# analog3.net
KiCad netlist of a schematic drawn in EAGLE
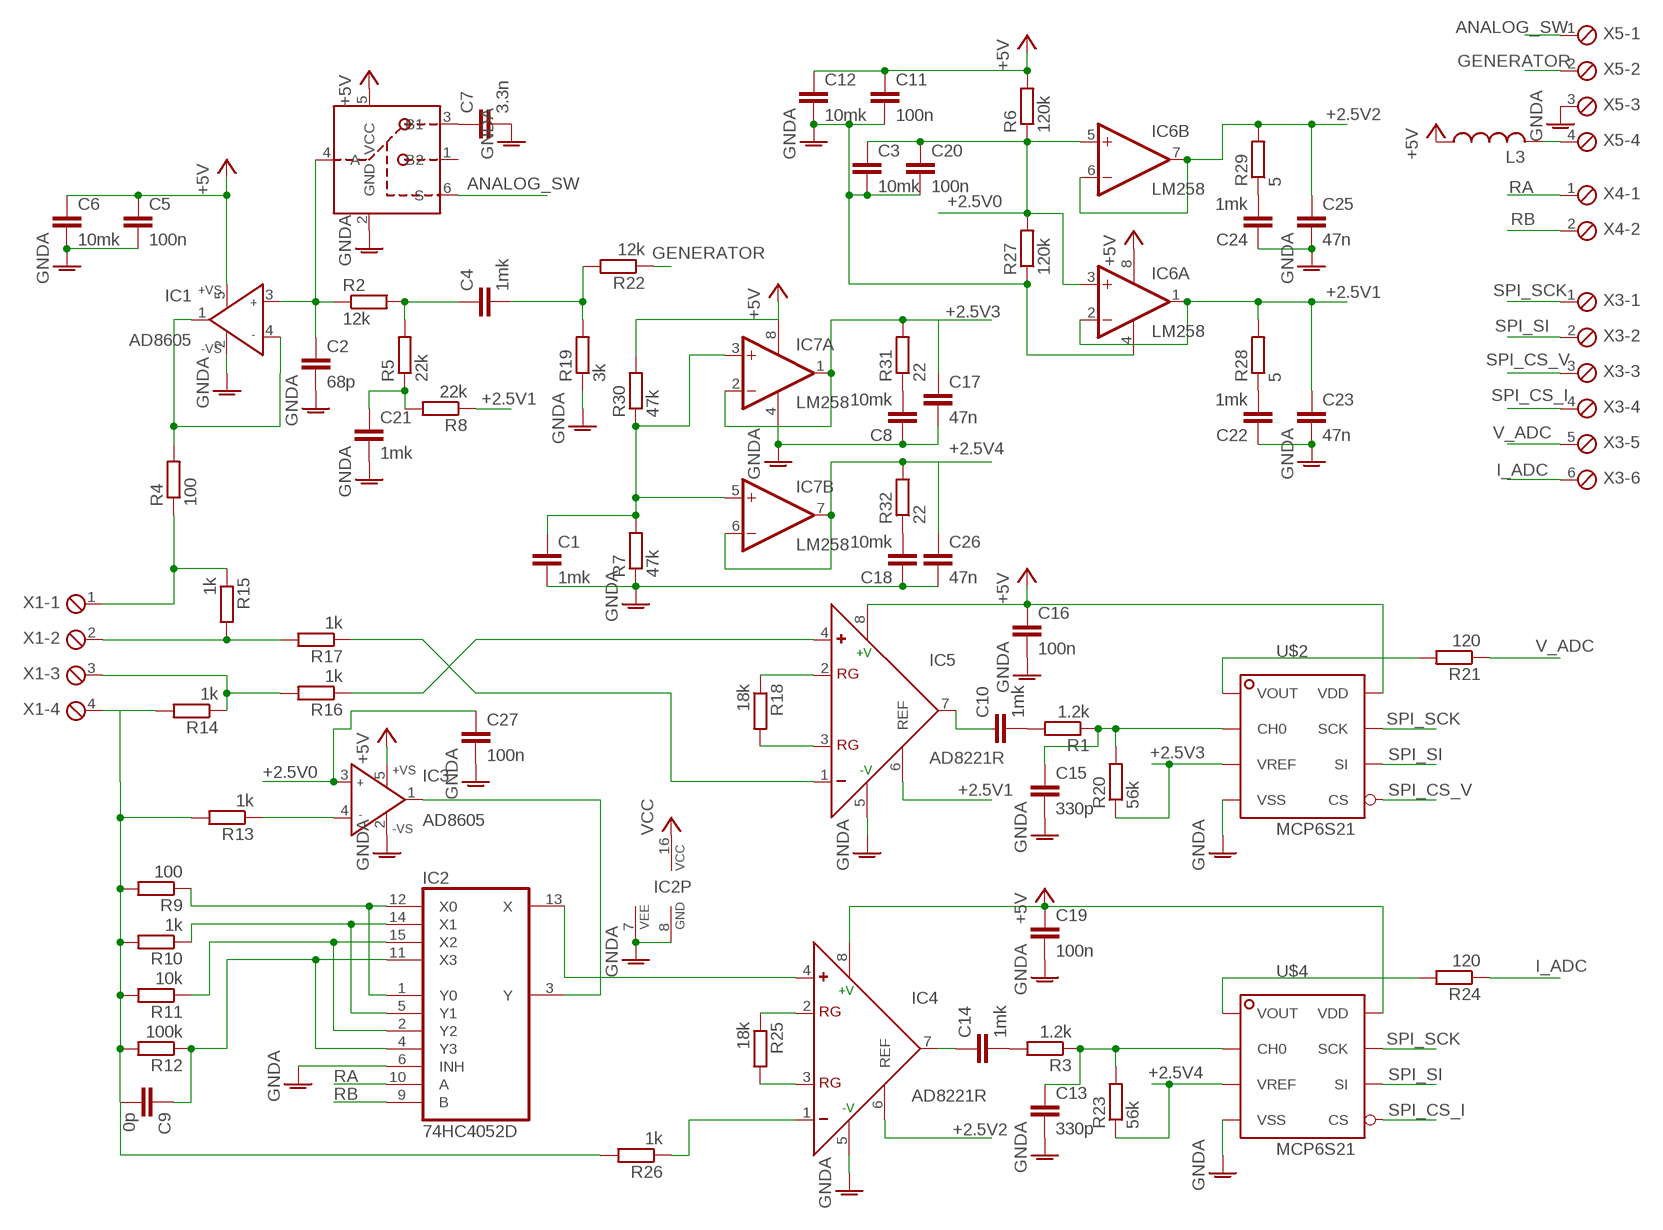
[diagram p0: schematic, sheet 1]

(export (version "E")
  (design (tool "Eeschema 10.0.6"))
  (components
    (comp (ref "C1")
      (value "1mk")
      (footprint "eagle-import:C0603")
      (libsource (lib "eagle-import") (part "C-EUC0603"))
    )
    (comp (ref "C2")
      (value "68p")
      (footprint "eagle-import:C0805")
      (libsource (lib "eagle-import") (part "C-EUC0805"))
    )
    (comp (ref "C3")
      (value "10mk")
      (footprint "eagle-import:C0805")
      (libsource (lib "eagle-import") (part "C-EUC0805"))
    )
    (comp (ref "C4")
      (value "1mk")
      (footprint "eagle-import:C0603")
      (libsource (lib "eagle-import") (part "C-EUC0603"))
    )
    (comp (ref "C5")
      (value "100n")
      (footprint "eagle-import:C0603")
      (libsource (lib "eagle-import") (part "C-EUC0603"))
    )
    (comp (ref "C6")
      (value "10mk")
      (footprint "eagle-import:C0805")
      (libsource (lib "eagle-import") (part "C-EUC0805"))
    )
    (comp (ref "C7")
      (value "3.3n")
      (footprint "eagle-import:C0805")
      (libsource (lib "eagle-import") (part "C-EUC0805"))
    )
    (comp (ref "C8")
      (value "10mk")
      (footprint "eagle-import:C0805")
      (libsource (lib "eagle-import") (part "C-EUC0805"))
    )
    (comp (ref "C9")
      (value "0p")
      (footprint "eagle-import:C0805")
      (libsource (lib "eagle-import") (part "C-EUC0805"))
    )
    (comp (ref "C10")
      (value "1mk")
      (footprint "eagle-import:C0603")
      (libsource (lib "eagle-import") (part "C-EUC0603"))
    )
    (comp (ref "C11")
      (value "100n")
      (footprint "eagle-import:C0603")
      (libsource (lib "eagle-import") (part "C-EUC0603"))
    )
    (comp (ref "C12")
      (value "10mk")
      (footprint "eagle-import:C0805")
      (libsource (lib "eagle-import") (part "C-EUC0805"))
    )
    (comp (ref "C13")
      (value "330p")
      (footprint "eagle-import:C0805")
      (libsource (lib "eagle-import") (part "C-EUC0805"))
    )
    (comp (ref "C14")
      (value "1mk")
      (footprint "eagle-import:C0603")
      (libsource (lib "eagle-import") (part "C-EUC0603"))
    )
    (comp (ref "C15")
      (value "330p")
      (footprint "eagle-import:C0805")
      (libsource (lib "eagle-import") (part "C-EUC0805"))
    )
    (comp (ref "C16")
      (value "100n")
      (footprint "eagle-import:C0603")
      (libsource (lib "eagle-import") (part "C-EUC0603"))
    )
    (comp (ref "C17")
      (value "47n")
      (footprint "eagle-import:C0805")
      (libsource (lib "eagle-import") (part "C-EUC0805"))
    )
    (comp (ref "C18")
      (value "10mk")
      (footprint "eagle-import:C0805")
      (libsource (lib "eagle-import") (part "C-EUC0805"))
    )
    (comp (ref "C19")
      (value "100n")
      (footprint "eagle-import:C0603")
      (libsource (lib "eagle-import") (part "C-EUC0603"))
    )
    (comp (ref "C20")
      (value "100n")
      (footprint "eagle-import:C0603")
      (libsource (lib "eagle-import") (part "C-EUC0603"))
    )
    (comp (ref "C21")
      (value "1mk")
      (footprint "eagle-import:C0603")
      (libsource (lib "eagle-import") (part "C-EUC0603"))
    )
    (comp (ref "C22")
      (value "1mk")
      (footprint "eagle-import:C0603")
      (libsource (lib "eagle-import") (part "C-EUC0603"))
    )
    (comp (ref "C23")
      (value "47n")
      (footprint "eagle-import:C0805")
      (libsource (lib "eagle-import") (part "C-EUC0805"))
    )
    (comp (ref "C24")
      (value "1mk")
      (footprint "eagle-import:C0603")
      (libsource (lib "eagle-import") (part "C-EUC0603"))
    )
    (comp (ref "C25")
      (value "47n")
      (footprint "eagle-import:C0805")
      (libsource (lib "eagle-import") (part "C-EUC0805"))
    )
    (comp (ref "C26")
      (value "47n")
      (footprint "eagle-import:C0805")
      (libsource (lib "eagle-import") (part "C-EUC0805"))
    )
    (comp (ref "C27")
      (value "100n")
      (footprint "eagle-import:C0603")
      (libsource (lib "eagle-import") (part "C-EUC0603"))
    )
    (comp (ref "IC1")
      (value "AD8605")
      (footprint "eagle-import:SOT23-5")
      (fields (field (name "MF") "ALTERA CORPORATION") (field (name "MPN") "AD8603AUJZ-REEL7"))
      (libsource (lib "eagle-import") (part "AD8603UJ"))
    )
    (comp (ref "IC2")
      (value "74HC4052D")
      (footprint "eagle-import:SO16")
      (libsource (lib "eagle-import") (part "4052D"))
    )
    (comp (ref "IC3")
      (value "AD8605")
      (footprint "eagle-import:SOT23-5")
      (fields (field (name "MF") "ALTERA CORPORATION") (field (name "MPN") "AD8603AUJZ-REEL7"))
      (libsource (lib "eagle-import") (part "AD8603UJ"))
    )
    (comp (ref "IC4")
      (value "AD8221R")
      (footprint "eagle-import:SO8")
      (fields (field (name "MPN") "AD620AR"))
      (libsource (lib "eagle-import") (part "AD8221R"))
    )
    (comp (ref "IC5")
      (value "AD8221R")
      (footprint "eagle-import:SO8")
      (fields (field (name "MPN") "AD620AR"))
      (libsource (lib "eagle-import") (part "AD8221R"))
    )
    (comp (ref "IC6")
      (value "LM258")
      (footprint "eagle-import:SO08")
      (libsource (lib "eagle-import") (part "LM358D"))
    )
    (comp (ref "IC7")
      (value "LM258")
      (footprint "eagle-import:SO08")
      (libsource (lib "eagle-import") (part "LM358D"))
    )
    (comp (ref "L3")
      (value "L-US0204/7")
      (footprint "eagle-import:0204_7")
      (libsource (lib "eagle-import") (part "L-US0204/7"))
    )
    (comp (ref "R1")
      (value "1.2k")
      (footprint "eagle-import:R0603")
      (libsource (lib "eagle-import") (part "R-EU_R0603"))
    )
    (comp (ref "R2")
      (value "12k")
      (footprint "eagle-import:R0603")
      (libsource (lib "eagle-import") (part "R-EU_R0603"))
    )
    (comp (ref "R3")
      (value "1.2k")
      (footprint "eagle-import:R0603")
      (libsource (lib "eagle-import") (part "R-EU_R0603"))
    )
    (comp (ref "R4")
      (value "100")
      (footprint "eagle-import:R0603")
      (libsource (lib "eagle-import") (part "R-EU_R0603"))
    )
    (comp (ref "R5")
      (value "22k")
      (footprint "eagle-import:R0603")
      (libsource (lib "eagle-import") (part "R-EU_R0603"))
    )
    (comp (ref "R6")
      (value "120k")
      (footprint "eagle-import:R0603")
      (libsource (lib "eagle-import") (part "R-EU_R0603"))
    )
    (comp (ref "R7")
      (value "47k")
      (footprint "eagle-import:R0603")
      (libsource (lib "eagle-import") (part "R-EU_R0603"))
    )
    (comp (ref "R8")
      (value "22k")
      (footprint "eagle-import:R0603")
      (libsource (lib "eagle-import") (part "R-EU_R0603"))
    )
    (comp (ref "R9")
      (value "100")
      (footprint "eagle-import:R0603")
      (libsource (lib "eagle-import") (part "R-EU_R0603"))
    )
    (comp (ref "R10")
      (value "1k")
      (footprint "eagle-import:R0603")
      (libsource (lib "eagle-import") (part "R-EU_R0603"))
    )
    (comp (ref "R11")
      (value "10k")
      (footprint "eagle-import:R0603")
      (libsource (lib "eagle-import") (part "R-EU_R0603"))
    )
    (comp (ref "R12")
      (value "100k")
      (footprint "eagle-import:R0603")
      (libsource (lib "eagle-import") (part "R-EU_R0603"))
    )
    (comp (ref "R13")
      (value "1k")
      (footprint "eagle-import:R0603")
      (libsource (lib "eagle-import") (part "R-EU_R0603"))
    )
    (comp (ref "R14")
      (value "1k")
      (footprint "eagle-import:R0603")
      (libsource (lib "eagle-import") (part "R-EU_R0603"))
    )
    (comp (ref "R15")
      (value "1k")
      (footprint "eagle-import:R0603")
      (libsource (lib "eagle-import") (part "R-EU_R0603"))
    )
    (comp (ref "R16")
      (value "1k")
      (footprint "eagle-import:R0603")
      (libsource (lib "eagle-import") (part "R-EU_R0603"))
    )
    (comp (ref "R17")
      (value "1k")
      (footprint "eagle-import:R0603")
      (libsource (lib "eagle-import") (part "R-EU_R0603"))
    )
    (comp (ref "R18")
      (value "18k")
      (footprint "eagle-import:R0603")
      (libsource (lib "eagle-import") (part "R-EU_R0603"))
    )
    (comp (ref "R19")
      (value "3k")
      (footprint "eagle-import:R0603")
      (libsource (lib "eagle-import") (part "R-EU_R0603"))
    )
    (comp (ref "R20")
      (value "56k")
      (footprint "eagle-import:R0603")
      (libsource (lib "eagle-import") (part "R-EU_R0603"))
    )
    (comp (ref "R21")
      (value "120")
      (footprint "eagle-import:R0603")
      (libsource (lib "eagle-import") (part "R-EU_R0603"))
    )
    (comp (ref "R22")
      (value "12k")
      (footprint "eagle-import:R0603")
      (libsource (lib "eagle-import") (part "R-EU_R0603"))
    )
    (comp (ref "R23")
      (value "56k")
      (footprint "eagle-import:R0603")
      (libsource (lib "eagle-import") (part "R-EU_R0603"))
    )
    (comp (ref "R24")
      (value "120")
      (footprint "eagle-import:R0603")
      (libsource (lib "eagle-import") (part "R-EU_R0603"))
    )
    (comp (ref "R25")
      (value "18k")
      (footprint "eagle-import:R0603")
      (libsource (lib "eagle-import") (part "R-EU_R0603"))
    )
    (comp (ref "R26")
      (value "1k")
      (footprint "eagle-import:R0603")
      (libsource (lib "eagle-import") (part "R-EU_R0603"))
    )
    (comp (ref "R27")
      (value "120k")
      (footprint "eagle-import:R0603")
      (libsource (lib "eagle-import") (part "R-EU_R0603"))
    )
    (comp (ref "R28")
      (value "5")
      (footprint "eagle-import:R0805")
      (libsource (lib "eagle-import") (part "R-EU_R0805"))
    )
    (comp (ref "R29")
      (value "5")
      (footprint "eagle-import:R0805")
      (libsource (lib "eagle-import") (part "R-EU_R0805"))
    )
    (comp (ref "R30")
      (value "47k")
      (footprint "eagle-import:R0603")
      (libsource (lib "eagle-import") (part "R-EU_R0603"))
    )
    (comp (ref "R31")
      (value "22")
      (footprint "eagle-import:R0805")
      (libsource (lib "eagle-import") (part "R-EU_R0805"))
    )
    (comp (ref "R32")
      (value "22")
      (footprint "eagle-import:R0805")
      (libsource (lib "eagle-import") (part "R-EU_R0805"))
    )
    (comp (ref "U$1")
      (value "SN74LVC1G3157DBVR")
      (footprint "eagle-import:SOT23-6")
      (libsource (lib "eagle-import") (part "SN74LVC1G3157DBVR"))
    )
    (comp (ref "U$2")
      (value "MCP6S21")
      (footprint "eagle-import:SO8")
      (libsource (lib "eagle-import") (part "MCP6S21"))
    )
    (comp (ref "U$4")
      (value "MCP6S21")
      (footprint "eagle-import:SO8")
      (libsource (lib "eagle-import") (part "MCP6S21"))
    )
    (comp (ref "X1")
      (value "MPT4")
      (footprint "eagle-import:4POL254")
      (libsource (lib "eagle-import") (part "MPT4"))
    )
    (comp (ref "X3")
      (value "MPT6")
      (footprint "eagle-import:6POL254")
      (libsource (lib "eagle-import") (part "MPT6"))
    )
    (comp (ref "X4")
      (value "MPT2")
      (footprint "eagle-import:2POL254")
      (libsource (lib "eagle-import") (part "MPT2"))
    )
    (comp (ref "X5")
      (value "MPT4")
      (footprint "eagle-import:4POL254")
      (libsource (lib "eagle-import") (part "MPT4"))
    )
  )
  (nets
    (net (code "1") (name "+5V") (class "Default")
      (node (ref "C11") (pin "1") (pinfunction "1_1") (pintype "passive"))
      (node (ref "C12") (pin "1") (pinfunction "1_1") (pintype "passive"))
      (node (ref "C16") (pin "1") (pinfunction "1_1") (pintype "passive"))
      (node (ref "C19") (pin "1") (pinfunction "1_1") (pintype "passive"))
      (node (ref "C5") (pin "1") (pinfunction "1_1") (pintype "passive"))
      (node (ref "C6") (pin "1") (pinfunction "1_1") (pintype "passive"))
      (node (ref "IC1") (pin "5") (pinfunction "+VS_5") (pintype "input"))
      (node (ref "IC3") (pin "5") (pinfunction "+VS_5") (pintype "input"))
      (node (ref "IC4") (pin "8") (pinfunction "+V_8") (pintype "power_in"))
      (node (ref "IC5") (pin "8") (pinfunction "+V_8") (pintype "power_in"))
      (node (ref "IC6") (pin "8") (pinfunction "V+_8") (pintype "power_in"))
      (node (ref "IC7") (pin "8") (pinfunction "V+_8") (pintype "power_in"))
      (node (ref "L3") (pin "1") (pinfunction "1_1") (pintype "passive"))
      (node (ref "R30") (pin "2") (pinfunction "2_2") (pintype "passive"))
      (node (ref "R6") (pin "2") (pinfunction "2_2") (pintype "passive"))
      (node (ref "U$1") (pin "5") (pinfunction "VCC_5") (pintype "power_in"))
      (node (ref "U$2") (pin "8") (pinfunction "VDD_8") (pintype "bidirectional"))
      (node (ref "U$4") (pin "8") (pinfunction "VDD_8") (pintype "bidirectional"))
    )
    (net (code "2") (name "/+2.5V0") (class "Default")
      (node (ref "C20") (pin "1") (pinfunction "1_1") (pintype "passive"))
      (node (ref "C27") (pin "1") (pinfunction "1_1") (pintype "passive"))
      (node (ref "C3") (pin "1") (pinfunction "1_1") (pintype "passive"))
      (node (ref "IC3") (pin "3") (pinfunction "IN+_3") (pintype "input"))
      (node (ref "IC6") (pin "3") (pinfunction "+IN_3") (pintype "input"))
      (node (ref "IC6") (pin "5") (pinfunction "+IN_5") (pintype "input"))
      (node (ref "R27") (pin "2") (pinfunction "2_2") (pintype "passive"))
      (node (ref "R6") (pin "1") (pinfunction "1_1") (pintype "passive"))
    )
    (net (code "3") (name "/+2.5V1") (class "Default")
      (node (ref "C23") (pin "1") (pinfunction "1_1") (pintype "passive"))
      (node (ref "IC5") (pin "6") (pinfunction "REF_6") (pintype "passive"))
      (node (ref "IC6") (pin "1") (pinfunction "OUT_1") (pintype "output"))
      (node (ref "IC6") (pin "2") (pinfunction "-IN_2") (pintype "input"))
      (node (ref "R28") (pin "2") (pinfunction "2_2") (pintype "passive"))
      (node (ref "R8") (pin "1") (pinfunction "1_1") (pintype "passive"))
    )
    (net (code "4") (name "/+2.5V2") (class "Default")
      (node (ref "C25") (pin "1") (pinfunction "1_1") (pintype "passive"))
      (node (ref "IC4") (pin "6") (pinfunction "REF_6") (pintype "passive"))
      (node (ref "IC6") (pin "6") (pinfunction "-IN_6") (pintype "input"))
      (node (ref "IC6") (pin "7") (pinfunction "OUT_7") (pintype "output"))
      (node (ref "R29") (pin "2") (pinfunction "2_2") (pintype "passive"))
    )
    (net (code "5") (name "/+2.5V3") (class "Default")
      (node (ref "C17") (pin "1") (pinfunction "1_1") (pintype "passive"))
      (node (ref "IC7") (pin "1") (pinfunction "OUT_1") (pintype "output"))
      (node (ref "IC7") (pin "2") (pinfunction "-IN_2") (pintype "input"))
      (node (ref "R20") (pin "1") (pinfunction "1_1") (pintype "passive"))
      (node (ref "R31") (pin "2") (pinfunction "2_2") (pintype "passive"))
      (node (ref "U$2") (pin "3") (pinfunction "VREF_3") (pintype "bidirectional"))
    )
    (net (code "6") (name "/+2.5V4") (class "Default")
      (node (ref "C26") (pin "1") (pinfunction "1_1") (pintype "passive"))
      (node (ref "IC7") (pin "6") (pinfunction "-IN_6") (pintype "input"))
      (node (ref "IC7") (pin "7") (pinfunction "OUT_7") (pintype "output"))
      (node (ref "R23") (pin "1") (pinfunction "1_1") (pintype "passive"))
      (node (ref "R32") (pin "2") (pinfunction "2_2") (pintype "passive"))
      (node (ref "U$4") (pin "3") (pinfunction "VREF_3") (pintype "bidirectional"))
    )
    (net (code "7") (name "/ANALOG_SW") (class "Default")
      (node (ref "U$1") (pin "6") (pinfunction "S_6") (pintype "bidirectional"))
      (node (ref "X5") (pin "1") (pinfunction "1_1") (pintype "passive"))
    )
    (net (code "8") (name "/GENERATOR") (class "Default")
      (node (ref "R22") (pin "1") (pinfunction "1_1") (pintype "passive"))
      (node (ref "X5") (pin "2") (pinfunction "1_2") (pintype "passive"))
    )
    (net (code "9") (name "/I_ADC") (class "Default")
      (node (ref "R24") (pin "1") (pinfunction "1_1") (pintype "passive"))
      (node (ref "X3") (pin "6") (pinfunction "1_6") (pintype "passive"))
    )
    (net (code "10") (name "/RA") (class "Default")
      (node (ref "IC2") (pin "10") (pinfunction "A_10") (pintype "input"))
      (node (ref "X4") (pin "1") (pinfunction "1_1") (pintype "passive"))
    )
    (net (code "11") (name "/RB") (class "Default")
      (node (ref "IC2") (pin "9") (pinfunction "B_9") (pintype "input"))
      (node (ref "X4") (pin "2") (pinfunction "1_2") (pintype "passive"))
    )
    (net (code "12") (name "/SPI_CS_I") (class "Default")
      (node (ref "U$4") (pin "5") (pinfunction "CS_5") (pintype "bidirectional"))
      (node (ref "X3") (pin "4") (pinfunction "1_4") (pintype "passive"))
    )
    (net (code "13") (name "/SPI_CS_V") (class "Default")
      (node (ref "U$2") (pin "5") (pinfunction "CS_5") (pintype "bidirectional"))
      (node (ref "X3") (pin "3") (pinfunction "1_3") (pintype "passive"))
    )
    (net (code "14") (name "/SPI_SCK") (class "Default")
      (node (ref "U$2") (pin "7") (pinfunction "SCK_7") (pintype "bidirectional"))
      (node (ref "U$4") (pin "7") (pinfunction "SCK_7") (pintype "bidirectional"))
      (node (ref "X3") (pin "1") (pinfunction "1_1") (pintype "passive"))
    )
    (net (code "15") (name "/SPI_SI") (class "Default")
      (node (ref "U$2") (pin "6") (pinfunction "SI_6") (pintype "bidirectional"))
      (node (ref "U$4") (pin "6") (pinfunction "SI_6") (pintype "bidirectional"))
      (node (ref "X3") (pin "2") (pinfunction "1_2") (pintype "passive"))
    )
    (net (code "16") (name "/V_ADC") (class "Default")
      (node (ref "R21") (pin "1") (pinfunction "1_1") (pintype "passive"))
      (node (ref "X3") (pin "5") (pinfunction "1_5") (pintype "passive"))
    )
    (net (code "17") (name "GNDA") (class "Default")
      (node (ref "C1") (pin "2") (pinfunction "2_2") (pintype "passive"))
      (node (ref "C11") (pin "2") (pinfunction "2_2") (pintype "passive"))
      (node (ref "C12") (pin "2") (pinfunction "2_2") (pintype "passive"))
      (node (ref "C13") (pin "2") (pinfunction "2_2") (pintype "passive"))
      (node (ref "C15") (pin "2") (pinfunction "2_2") (pintype "passive"))
      (node (ref "C16") (pin "2") (pinfunction "2_2") (pintype "passive"))
      (node (ref "C17") (pin "2") (pinfunction "2_2") (pintype "passive"))
      (node (ref "C18") (pin "1") (pinfunction "1_1") (pintype "passive"))
      (node (ref "C19") (pin "2") (pinfunction "2_2") (pintype "passive"))
      (node (ref "C2") (pin "2") (pinfunction "2_2") (pintype "passive"))
      (node (ref "C20") (pin "2") (pinfunction "2_2") (pintype "passive"))
      (node (ref "C21") (pin "2") (pinfunction "2_2") (pintype "passive"))
      (node (ref "C22") (pin "1") (pinfunction "1_1") (pintype "passive"))
      (node (ref "C23") (pin "2") (pinfunction "2_2") (pintype "passive"))
      (node (ref "C24") (pin "1") (pinfunction "1_1") (pintype "passive"))
      (node (ref "C25") (pin "2") (pinfunction "2_2") (pintype "passive"))
      (node (ref "C26") (pin "2") (pinfunction "2_2") (pintype "passive"))
      (node (ref "C27") (pin "2") (pinfunction "2_2") (pintype "passive"))
      (node (ref "C3") (pin "2") (pinfunction "2_2") (pintype "passive"))
      (node (ref "C5") (pin "2") (pinfunction "2_2") (pintype "passive"))
      (node (ref "C6") (pin "2") (pinfunction "2_2") (pintype "passive"))
      (node (ref "C7") (pin "2") (pinfunction "2_2") (pintype "passive"))
      (node (ref "C8") (pin "1") (pinfunction "1_1") (pintype "passive"))
      (node (ref "IC1") (pin "2") (pinfunction "-VS_2") (pintype "input"))
      (node (ref "IC2") (pin "6") (pinfunction "INH_6") (pintype "input"))
      (node (ref "IC2") (pin "7") (pinfunction "VEE_7") (pintype "power_in"))
      (node (ref "IC2") (pin "8") (pinfunction "GND_8") (pintype "power_in"))
      (node (ref "IC3") (pin "2") (pinfunction "-VS_2") (pintype "input"))
      (node (ref "IC4") (pin "5") (pinfunction "-V_5") (pintype "power_in"))
      (node (ref "IC5") (pin "5") (pinfunction "-V_5") (pintype "power_in"))
      (node (ref "IC6") (pin "4") (pinfunction "V-_4") (pintype "power_in"))
      (node (ref "IC7") (pin "4") (pinfunction "V-_4") (pintype "power_in"))
      (node (ref "R19") (pin "1") (pinfunction "1_1") (pintype "passive"))
      (node (ref "R27") (pin "1") (pinfunction "1_1") (pintype "passive"))
      (node (ref "R7") (pin "1") (pinfunction "1_1") (pintype "passive"))
      (node (ref "U$1") (pin "2") (pinfunction "GND_2") (pintype "power_in"))
      (node (ref "U$2") (pin "4") (pinfunction "VSS_4") (pintype "bidirectional"))
      (node (ref "U$4") (pin "4") (pinfunction "VSS_4") (pintype "bidirectional"))
      (node (ref "X5") (pin "3") (pinfunction "1_3") (pintype "passive"))
    )
    (net (code "18") (name "Net-(C4-Pad1)") (class "Default")
      (node (ref "C4") (pin "1") (pinfunction "1_1") (pintype "passive"))
      (node (ref "R2") (pin "2") (pinfunction "2_2") (pintype "passive"))
      (node (ref "R5") (pin "2") (pinfunction "2_2") (pintype "passive"))
    )
    (net (code "19") (name "Net-(C4-Pad2)") (class "Default")
      (node (ref "C4") (pin "2") (pinfunction "2_2") (pintype "passive"))
      (node (ref "R19") (pin "2") (pinfunction "2_2") (pintype "passive"))
      (node (ref "R22") (pin "2") (pinfunction "2_2") (pintype "passive"))
    )
    (net (code "20") (name "Net-(C8-Pad2)") (class "Default")
      (node (ref "C8") (pin "2") (pinfunction "2_2") (pintype "passive"))
      (node (ref "R31") (pin "1") (pinfunction "1_1") (pintype "passive"))
    )
    (net (code "21") (name "Net-(C10-Pad2)") (class "Default")
      (node (ref "C10") (pin "2") (pinfunction "2_2") (pintype "passive"))
      (node (ref "R1") (pin "2") (pinfunction "2_2") (pintype "passive"))
    )
    (net (code "22") (name "Net-(C14-Pad2)") (class "Default")
      (node (ref "C14") (pin "2") (pinfunction "2_2") (pintype "passive"))
      (node (ref "R3") (pin "2") (pinfunction "2_2") (pintype "passive"))
    )
    (net (code "23") (name "Net-(C18-Pad2)") (class "Default")
      (node (ref "C18") (pin "2") (pinfunction "2_2") (pintype "passive"))
      (node (ref "R32") (pin "1") (pinfunction "1_1") (pintype "passive"))
    )
    (net (code "24") (name "Net-(C21-Pad1)") (class "Default")
      (node (ref "C21") (pin "1") (pinfunction "1_1") (pintype "passive"))
      (node (ref "R5") (pin "1") (pinfunction "1_1") (pintype "passive"))
      (node (ref "R8") (pin "2") (pinfunction "2_2") (pintype "passive"))
    )
    (net (code "25") (name "Net-(C22-Pad2)") (class "Default")
      (node (ref "C22") (pin "2") (pinfunction "2_2") (pintype "passive"))
      (node (ref "R28") (pin "1") (pinfunction "1_1") (pintype "passive"))
    )
    (net (code "26") (name "Net-(C24-Pad2)") (class "Default")
      (node (ref "C24") (pin "2") (pinfunction "2_2") (pintype "passive"))
      (node (ref "R29") (pin "1") (pinfunction "1_1") (pintype "passive"))
    )
    (net (code "27") (name "Net-(IC1-IN+)") (class "Default")
      (node (ref "C2") (pin "1") (pinfunction "1_1") (pintype "passive"))
      (node (ref "IC1") (pin "3") (pinfunction "IN+_3") (pintype "input"))
      (node (ref "R2") (pin "1") (pinfunction "1_1") (pintype "passive"))
      (node (ref "U$1") (pin "4") (pinfunction "A_4") (pintype "bidirectional"))
    )
    (net (code "28") (name "Net-(IC1-IN-)") (class "Default")
      (node (ref "IC1") (pin "1") (pinfunction "OUT_1") (pintype "output"))
      (node (ref "IC1") (pin "4") (pinfunction "IN-_4") (pintype "input"))
      (node (ref "R4") (pin "2") (pinfunction "2_2") (pintype "passive"))
    )
    (net (code "29") (name "Net-(IC2A-X)") (class "Default")
      (node (ref "IC2") (pin "13") (pinfunction "X_13") (pintype "bidirectional"))
      (node (ref "IC4") (pin "4") (pinfunction "+_4") (pintype "input"))
    )
    (net (code "30") (name "Net-(IC2A-X0)") (class "Default")
      (node (ref "IC2") (pin "1") (pinfunction "Y0_1") (pintype "bidirectional"))
      (node (ref "IC2") (pin "12") (pinfunction "X0_12") (pintype "bidirectional"))
      (node (ref "R9") (pin "1") (pinfunction "1_1") (pintype "passive"))
    )
    (net (code "31") (name "Net-(IC2A-X1)") (class "Default")
      (node (ref "IC2") (pin "14") (pinfunction "X1_14") (pintype "bidirectional"))
      (node (ref "IC2") (pin "5") (pinfunction "Y1_5") (pintype "bidirectional"))
      (node (ref "R10") (pin "1") (pinfunction "1_1") (pintype "passive"))
    )
    (net (code "32") (name "Net-(IC2A-X2)") (class "Default")
      (node (ref "IC2") (pin "15") (pinfunction "X2_15") (pintype "bidirectional"))
      (node (ref "IC2") (pin "2") (pinfunction "Y2_2") (pintype "bidirectional"))
      (node (ref "R11") (pin "1") (pinfunction "1_1") (pintype "passive"))
    )
    (net (code "33") (name "Net-(IC2A-X3)") (class "Default")
      (node (ref "C9") (pin "1") (pinfunction "1_1") (pintype "passive"))
      (node (ref "IC2") (pin "11") (pinfunction "X3_11") (pintype "bidirectional"))
      (node (ref "IC2") (pin "4") (pinfunction "Y3_4") (pintype "bidirectional"))
      (node (ref "R12") (pin "1") (pinfunction "1_1") (pintype "passive"))
    )
    (net (code "34") (name "Net-(IC2A-Y)") (class "Default")
      (node (ref "IC2") (pin "3") (pinfunction "Y_3") (pintype "bidirectional"))
      (node (ref "IC3") (pin "1") (pinfunction "OUT_1") (pintype "output"))
    )
    (net (code "35") (name "Net-(IC3-IN-)") (class "Default")
      (node (ref "IC3") (pin "4") (pinfunction "IN-_4") (pintype "input"))
      (node (ref "R13") (pin "1") (pinfunction "1_1") (pintype "passive"))
    )
    (net (code "36") (name "Net-(IC4--)") (class "Default")
      (node (ref "IC4") (pin "1") (pinfunction "-_1") (pintype "input"))
      (node (ref "R26") (pin "1") (pinfunction "1_1") (pintype "passive"))
    )
    (net (code "37") (name "Net-(IC4-OUT)") (class "Default")
      (node (ref "C14") (pin "1") (pinfunction "1_1") (pintype "passive"))
      (node (ref "IC4") (pin "7") (pinfunction "OUT_7") (pintype "output"))
    )
    (net (code "38") (name "Net-(IC4-RG-Pad2)") (class "Default")
      (node (ref "IC4") (pin "2") (pinfunction "RG_2") (pintype "passive"))
      (node (ref "R25") (pin "1") (pinfunction "1_1") (pintype "passive"))
    )
    (net (code "39") (name "Net-(IC4-RG-Pad3)") (class "Default")
      (node (ref "IC4") (pin "3") (pinfunction "RG_3") (pintype "passive"))
      (node (ref "R25") (pin "2") (pinfunction "2_2") (pintype "passive"))
    )
    (net (code "40") (name "Net-(IC5-+)") (class "Default")
      (node (ref "IC5") (pin "4") (pinfunction "+_4") (pintype "input"))
      (node (ref "R16") (pin "1") (pinfunction "1_1") (pintype "passive"))
    )
    (net (code "41") (name "Net-(IC5--)") (class "Default")
      (node (ref "IC5") (pin "1") (pinfunction "-_1") (pintype "input"))
      (node (ref "R17") (pin "1") (pinfunction "1_1") (pintype "passive"))
    )
    (net (code "42") (name "Net-(IC5-OUT)") (class "Default")
      (node (ref "C10") (pin "1") (pinfunction "1_1") (pintype "passive"))
      (node (ref "IC5") (pin "7") (pinfunction "OUT_7") (pintype "output"))
    )
    (net (code "43") (name "Net-(IC5-RG-Pad2)") (class "Default")
      (node (ref "IC5") (pin "2") (pinfunction "RG_2") (pintype "passive"))
      (node (ref "R18") (pin "1") (pinfunction "1_1") (pintype "passive"))
    )
    (net (code "44") (name "Net-(IC5-RG-Pad3)") (class "Default")
      (node (ref "IC5") (pin "3") (pinfunction "RG_3") (pintype "passive"))
      (node (ref "R18") (pin "2") (pinfunction "2_2") (pintype "passive"))
    )
    (net (code "45") (name "Net-(IC7A-+IN)") (class "Default")
      (node (ref "C1") (pin "1") (pinfunction "1_1") (pintype "passive"))
      (node (ref "IC7") (pin "3") (pinfunction "+IN_3") (pintype "input"))
      (node (ref "IC7") (pin "5") (pinfunction "+IN_5") (pintype "input"))
      (node (ref "R30") (pin "1") (pinfunction "1_1") (pintype "passive"))
      (node (ref "R7") (pin "2") (pinfunction "2_2") (pintype "passive"))
    )
    (net (code "46") (name "Net-(R15-Pad1)") (class "Default")
      (node (ref "R15") (pin "1") (pinfunction "1_1") (pintype "passive"))
      (node (ref "R4") (pin "1") (pinfunction "1_1") (pintype "passive"))
      (node (ref "X1") (pin "1") (pinfunction "1_1") (pintype "passive"))
    )
    (net (code "47") (name "Net-(U$1-B1)") (class "Default")
      (node (ref "C7") (pin "1") (pinfunction "1_1") (pintype "passive"))
      (node (ref "U$1") (pin "3") (pinfunction "B1_3") (pintype "bidirectional"))
    )
    (net (code "48") (name "Net-(U$2-CH0)") (class "Default")
      (node (ref "C15") (pin "1") (pinfunction "1_1") (pintype "passive"))
      (node (ref "R1") (pin "1") (pinfunction "1_1") (pintype "passive"))
      (node (ref "R20") (pin "2") (pinfunction "2_2") (pintype "passive"))
      (node (ref "U$2") (pin "2") (pinfunction "CH0_2") (pintype "bidirectional"))
    )
    (net (code "49") (name "Net-(U$2-VOUT)") (class "Default")
      (node (ref "R21") (pin "2") (pinfunction "2_2") (pintype "passive"))
      (node (ref "U$2") (pin "1") (pinfunction "VOUT_1") (pintype "output"))
    )
    (net (code "50") (name "Net-(U$4-CH0)") (class "Default")
      (node (ref "C13") (pin "1") (pinfunction "1_1") (pintype "passive"))
      (node (ref "R23") (pin "2") (pinfunction "2_2") (pintype "passive"))
      (node (ref "R3") (pin "1") (pinfunction "1_1") (pintype "passive"))
      (node (ref "U$4") (pin "2") (pinfunction "CH0_2") (pintype "bidirectional"))
    )
    (net (code "51") (name "Net-(U$4-VOUT)") (class "Default")
      (node (ref "R24") (pin "2") (pinfunction "2_2") (pintype "passive"))
      (node (ref "U$4") (pin "1") (pinfunction "VOUT_1") (pintype "output"))
    )
    (net (code "52") (name "Net-(X1B-1)") (class "Default")
      (node (ref "R15") (pin "2") (pinfunction "2_2") (pintype "passive"))
      (node (ref "R17") (pin "2") (pinfunction "2_2") (pintype "passive"))
      (node (ref "X1") (pin "2") (pinfunction "1_2") (pintype "passive"))
    )
    (net (code "53") (name "Net-(X1C-1)") (class "Default")
      (node (ref "R14") (pin "1") (pinfunction "1_1") (pintype "passive"))
      (node (ref "R16") (pin "2") (pinfunction "2_2") (pintype "passive"))
      (node (ref "X1") (pin "3") (pinfunction "1_3") (pintype "passive"))
    )
    (net (code "54") (name "Net-(X1D-1)") (class "Default")
      (node (ref "C9") (pin "2") (pinfunction "2_2") (pintype "passive"))
      (node (ref "R10") (pin "2") (pinfunction "2_2") (pintype "passive"))
      (node (ref "R11") (pin "2") (pinfunction "2_2") (pintype "passive"))
      (node (ref "R12") (pin "2") (pinfunction "2_2") (pintype "passive"))
      (node (ref "R13") (pin "2") (pinfunction "2_2") (pintype "passive"))
      (node (ref "R14") (pin "2") (pinfunction "2_2") (pintype "passive"))
      (node (ref "R26") (pin "2") (pinfunction "2_2") (pintype "passive"))
      (node (ref "R9") (pin "2") (pinfunction "2_2") (pintype "passive"))
      (node (ref "X1") (pin "4") (pinfunction "1_4") (pintype "passive"))
    )
    (net (code "55") (name "Net-(X5D-1)") (class "Default")
      (node (ref "L3") (pin "2") (pinfunction "2_2") (pintype "passive"))
      (node (ref "X5") (pin "4") (pinfunction "1_4") (pintype "passive"))
    )
    (net (code "56") (name "VCC") (class "Default")
      (node (ref "IC2") (pin "16") (pinfunction "VCC_16") (pintype "power_in"))
    )
    (net (code "57") (name "unconnected-(U$1-B2-Pad1)") (class "Default")
      (node (ref "U$1") (pin "1") (pinfunction "B2_1") (pintype "bidirectional"))
    )
  )
)
